# Temp_Sensor.net
KiCad netlist of a schematic drawn in EAGLE
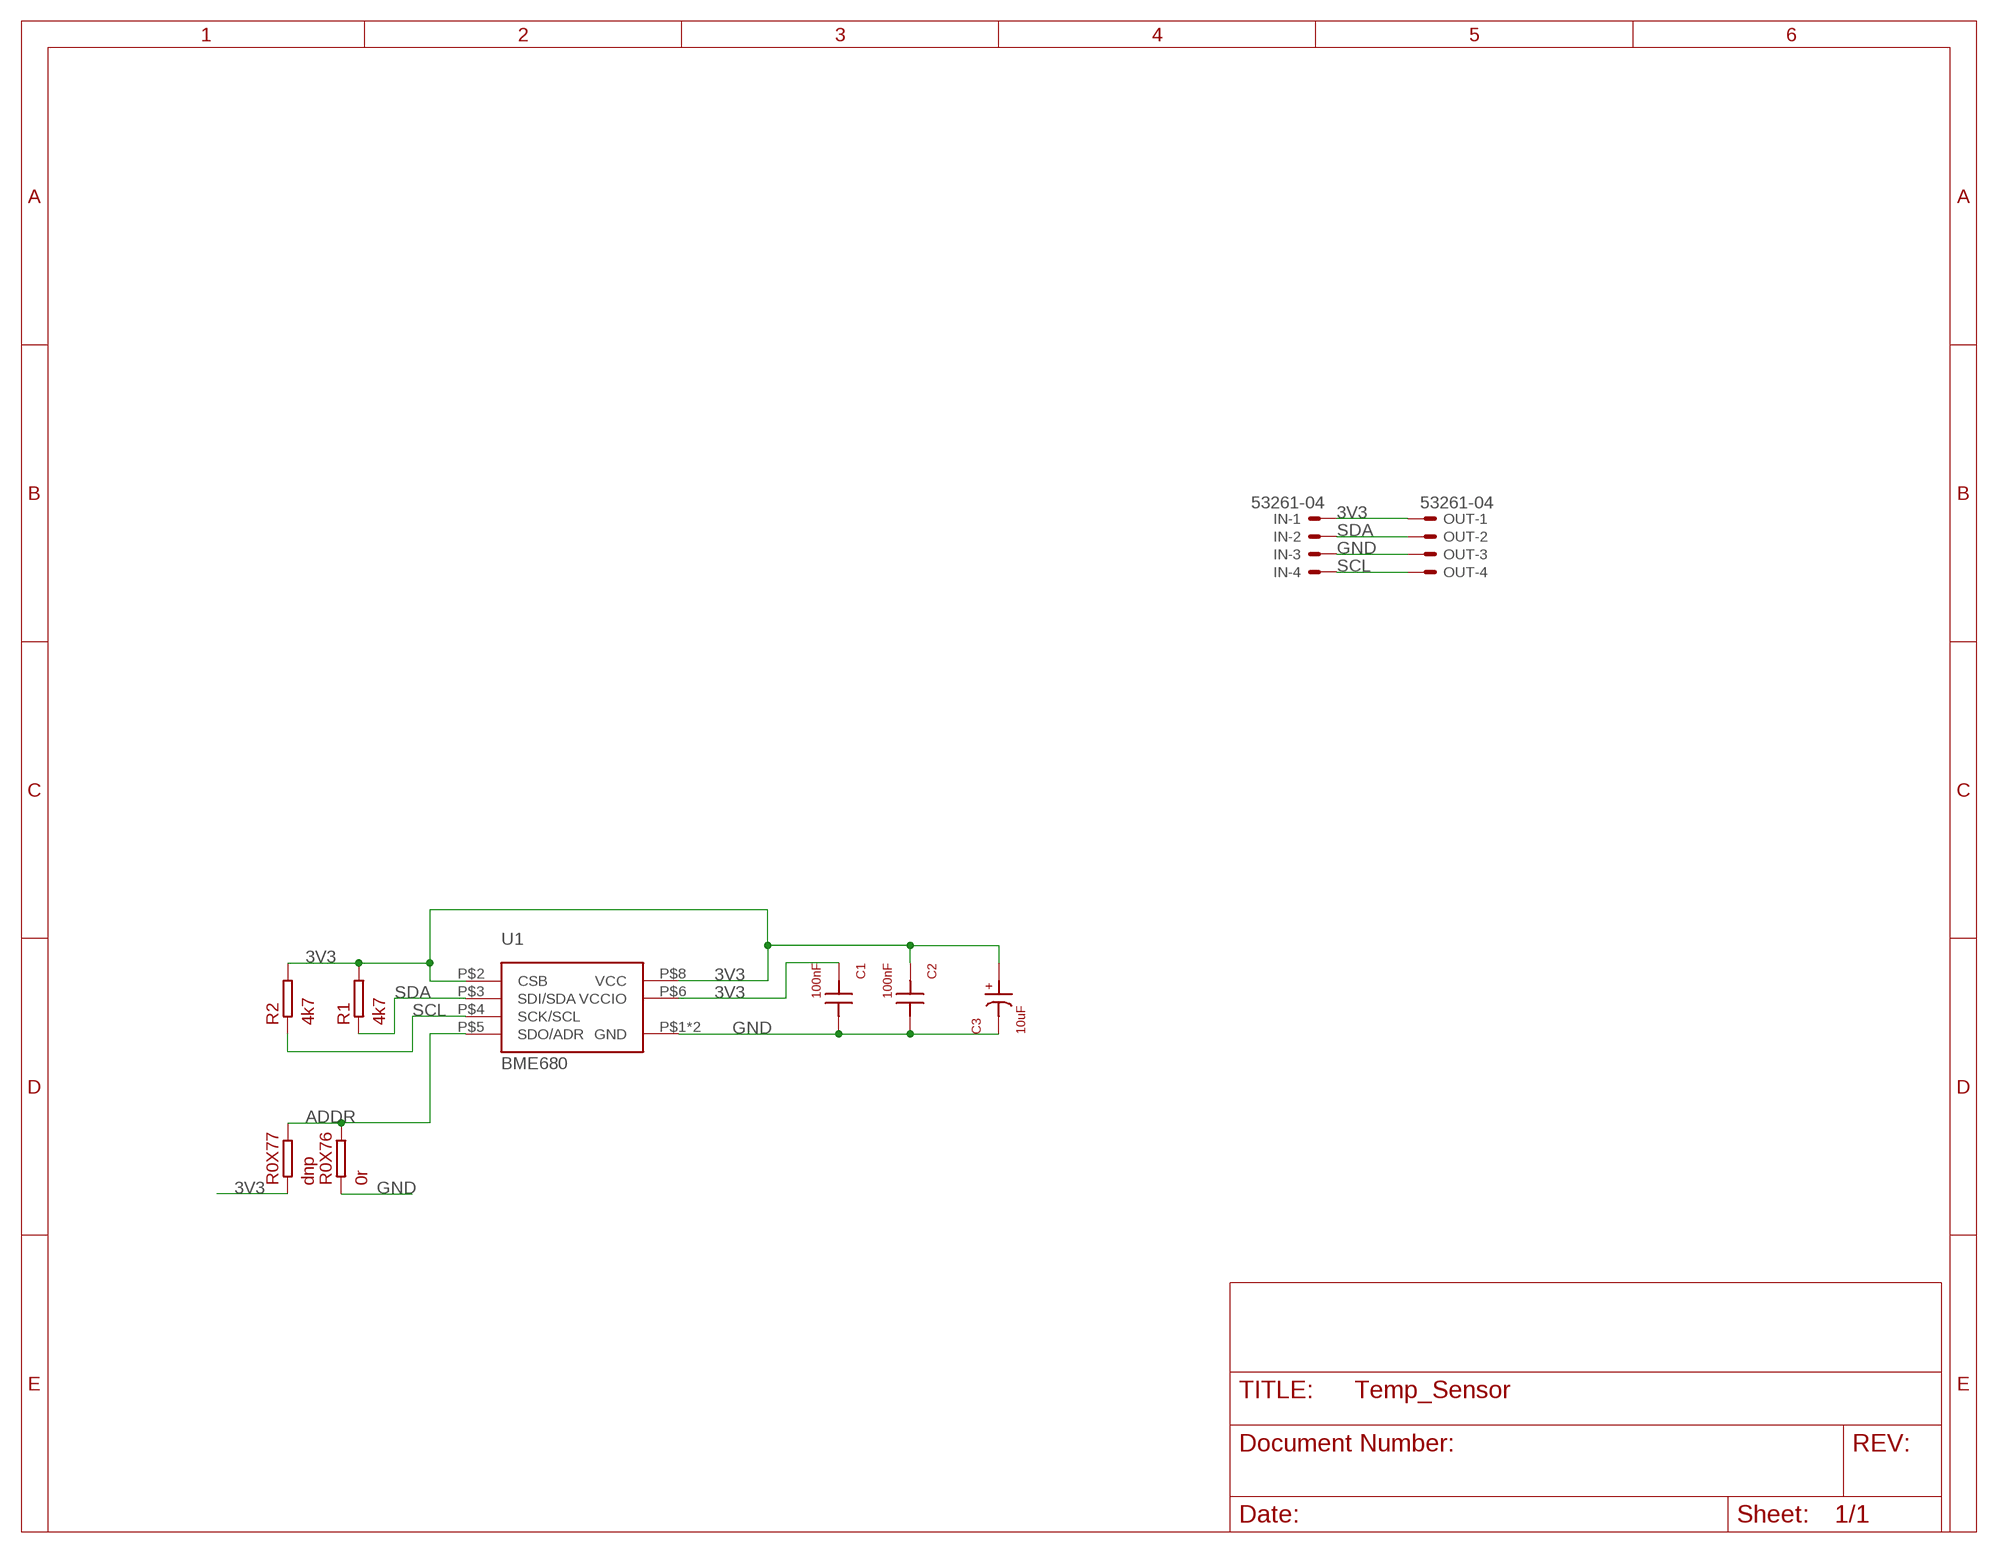
[diagram p0: schematic, sheet 1]

(export (version "E")
  (design (tool "Eeschema 10.0.6"))
  (components
    (comp (ref "C1")
      (value "100nF")
      (footprint "eagle-import:SMD_0402")
      (libsource (lib "eagle-import") (part "CAP_NP_0402"))
    )
    (comp (ref "C2")
      (value "100nF")
      (footprint "eagle-import:SMD_0402")
      (libsource (lib "eagle-import") (part "CAP_NP_0402"))
    )
    (comp (ref "C3")
      (value "10uF")
      (footprint "eagle-import:CAP_POL_1206")
      (libsource (lib "eagle-import") (part "CAP_POL_SMD_1206"))
    )
    (comp (ref "IN")
      (value "53261-04")
      (footprint "eagle-import:53261-04")
      (fields (field (name "MF") "MOLEX"))
      (libsource (lib "eagle-import") (part "53?-04261"))
    )
    (comp (ref "OUT")
      (value "53261-04")
      (footprint "eagle-import:53261-04")
      (fields (field (name "MF") "MOLEX"))
      (libsource (lib "eagle-import") (part "53?-04261"))
    )
    (comp (ref "R0X76")
      (value "0r")
      (footprint "eagle-import:SMD_0402")
      (libsource (lib "eagle-import") (part "RESISTOR_0402"))
    )
    (comp (ref "R0X77")
      (value "dnp")
      (footprint "eagle-import:SMD_0402")
      (libsource (lib "eagle-import") (part "RESISTOR_0402"))
    )
    (comp (ref "R1")
      (value "4k7")
      (footprint "eagle-import:SMD_0402")
      (libsource (lib "eagle-import") (part "RESISTOR_0402"))
    )
    (comp (ref "R2")
      (value "4k7")
      (footprint "eagle-import:SMD_0402")
      (libsource (lib "eagle-import") (part "RESISTOR_0402"))
    )
    (comp (ref "U1")
      (value "BME680")
      (footprint "eagle-import:BOSCH_LGA8")
      (libsource (lib "eagle-import") (part "BME680_GAS_AQ/BARO/TEMP/HUMID-I2C-SPI"))
    )
  )
  (nets
    (net (code "1") (name "/3V3") (class "Default")
      (node (ref "C1") (pin "P$1") (pinfunction "P$1_P$1") (pintype "passive"))
      (node (ref "C2") (pin "P$1") (pinfunction "P$1_P$1") (pintype "passive"))
      (node (ref "C3") (pin "P") (pinfunction "P_P") (pintype "passive"))
      (node (ref "IN") (pin "1") (pinfunction "S_1") (pintype "passive"))
      (node (ref "OUT") (pin "1") (pinfunction "S_1") (pintype "passive"))
      (node (ref "R0X77") (pin "P$1") (pinfunction "P$1_P$1") (pintype "passive"))
      (node (ref "R1") (pin "P$2") (pinfunction "P$2_P$2") (pintype "passive"))
      (node (ref "R2") (pin "P$2") (pinfunction "P$2_P$2") (pintype "passive"))
      (node (ref "U1") (pin "P$2") (pinfunction "CSB_P$2") (pintype "input"))
      (node (ref "U1") (pin "P$6") (pinfunction "VCCIO_P$6") (pintype "power_in"))
      (node (ref "U1") (pin "P$8") (pinfunction "VCC_P$8") (pintype "power_in"))
    )
    (net (code "2") (name "/ADDR") (class "Default")
      (node (ref "R0X76") (pin "P$2") (pinfunction "P$2_P$2") (pintype "passive"))
      (node (ref "R0X77") (pin "P$2") (pinfunction "P$2_P$2") (pintype "passive"))
      (node (ref "U1") (pin "P$5") (pinfunction "SDO/ADR_P$5") (pintype "output"))
    )
    (net (code "3") (name "/GND") (class "Default")
      (node (ref "C1") (pin "P$2") (pinfunction "P$2_P$2") (pintype "passive"))
      (node (ref "C2") (pin "P$2") (pinfunction "P$2_P$2") (pintype "passive"))
      (node (ref "C3") (pin "N") (pinfunction "N_N") (pintype "passive"))
      (node (ref "IN") (pin "3") (pinfunction "S_3") (pintype "passive"))
      (node (ref "OUT") (pin "3") (pinfunction "S_3") (pintype "passive"))
      (node (ref "R0X76") (pin "P$1") (pinfunction "P$1_P$1") (pintype "passive"))
      (node (ref "U1") (pin "P$1") (pinfunction "GND_P$1") (pintype "power_in"))
      (node (ref "U1") (pin "P$7") (pinfunction "GND_P$7") (pintype "power_in"))
    )
    (net (code "4") (name "/SCL") (class "Default")
      (node (ref "IN") (pin "4") (pinfunction "S_4") (pintype "passive"))
      (node (ref "OUT") (pin "4") (pinfunction "S_4") (pintype "passive"))
      (node (ref "R2") (pin "P$1") (pinfunction "P$1_P$1") (pintype "passive"))
      (node (ref "U1") (pin "P$4") (pinfunction "SCK/SCL_P$4") (pintype "input"))
    )
    (net (code "5") (name "/SDA") (class "Default")
      (node (ref "IN") (pin "2") (pinfunction "S_2") (pintype "passive"))
      (node (ref "OUT") (pin "2") (pinfunction "S_2") (pintype "passive"))
      (node (ref "R1") (pin "P$1") (pinfunction "P$1_P$1") (pintype "passive"))
      (node (ref "U1") (pin "P$3") (pinfunction "SDI/SDA_P$3") (pintype "bidirectional"))
    )
  )
)
